# Atmega328.net
KiCad netlist of a schematic drawn in Altium Designer
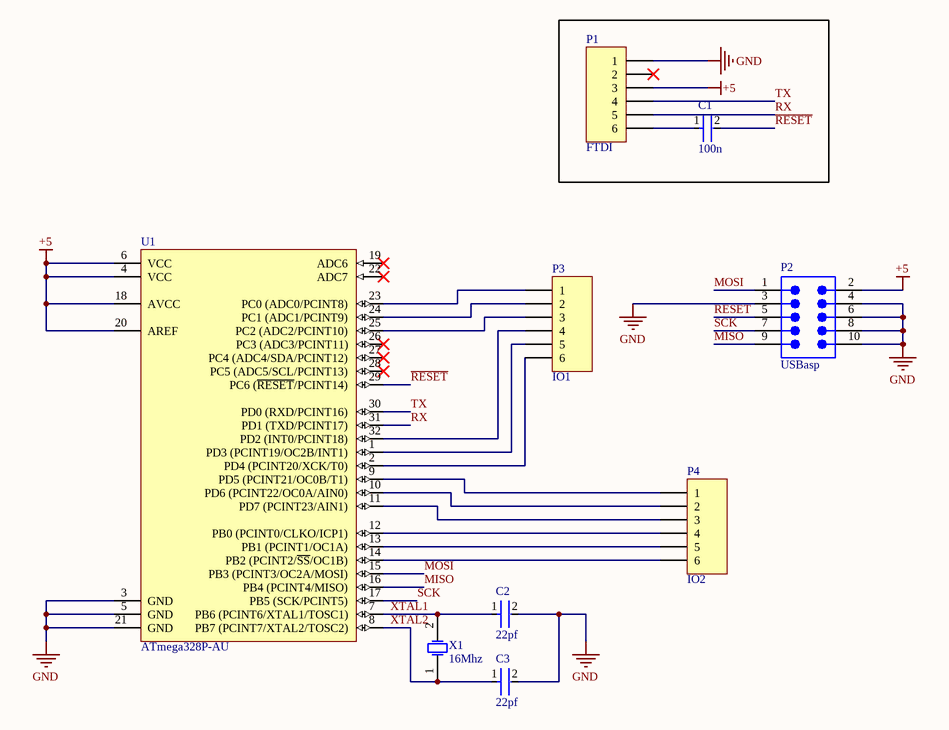
[diagram p0: Atmega328.SchDoc]

(export (version "E")
  (design (tool "Eeschema 10.0.6"))
  (components
    (comp (ref "C1")
      (value "100n")
      (footprint "FP-0805-L_2_01_0_2-W_1_25-IPC_B")
      (description "General Purpose Ceramic Capacitor, 0805, 100nF, 10%, X7R, 15%, 100V")
      (fields (field (name "VOLTAGE") "100V") (field (name "TOLERANCE") "10%"))
      (libsource (lib "Altium Content Vault") (part "b4654b650e69147ec39a6b967a45e02"))
    )
    (comp (ref "C2")
      (value "22pf")
      (footprint "FP-C0805C-DN-MFG")
      (description "Capacitor; Ceramic; Cap; 22.0pF; Tol 5%; SMT; Vol-Rtg 50V; C0G; Tape and Reel")
      (fields
        (field (name "OCTOPART") "https://octopart.com/c0805c220j5gactu-kemet-145470")
        (field (name "MANUFACTURER") "KEMET")
      )
      (libsource (lib "Altium Content Vault") (part "b4654b650e69147ec39a6b967a45e02"))
    )
    (comp (ref "C3")
      (value "22pf")
      (footprint "FP-C0805C-DN-MFG")
      (description "Capacitor; Ceramic; Cap; 22.0pF; Tol 5%; SMT; Vol-Rtg 50V; C0G; Tape and Reel")
      (fields
        (field (name "OCTOPART") "https://octopart.com/c0805c220j5gactu-kemet-145470")
        (field (name "MANUFACTURER") "KEMET")
      )
      (libsource (lib "Altium Content Vault") (part "b4654b650e69147ec39a6b967a45e02"))
    )
    (comp (ref "P1")
      (value "FTDI")
      (footprint "MHDR1X6")
      (description "Header, 6-Pin")
      (fields (field (name "PUBLISHER") "Altium Limited"))
      (libsource (lib "") (part "MHDR1X6_1"))
    )
    (comp (ref "P2")
      (value "USBasp")
      (footprint "61201021621")
      (libsource (lib "Altium Content Vault") (part "Header_Male_2R_10P"))
    )
    (comp (ref "P3")
      (value "IO1")
      (footprint "MHDR1X6")
      (description "Header, 6-Pin")
      (fields (field (name "PUBLISHER") "Altium Limited"))
      (libsource (lib "Miscellaneous Connectors") (part "MHDR1X6"))
    )
    (comp (ref "P4")
      (value "IO2")
      (footprint "MHDR1X6")
      (description "Header, 6-Pin")
      (fields (field (name "PUBLISHER") "Altium Limited"))
      (libsource (lib "Miscellaneous Connectors") (part "MHDR1X6"))
    )
    (comp (ref "U1")
      (value "ATmega328P-AU")
      (footprint "32A_M")
      (libsource (lib "Altium Content Vault") (part "MC-8B-ATM48-SQ32"))
    )
    (comp (ref "X1")
      (value "16Mhz")
      (footprint "FOX-FOXSDLF160-20_V")
      (libsource (lib "Altium Content Vault") (part "XTAL_1-2-2"))
    )
  )
  (nets
    (net (code "1") (name "+5") (class "Default")
      (node (ref "P1") (pin "3") (pinfunction "3_3") (pintype "passive"))
      (node (ref "P2") (pin "2") (pinfunction "2_2") (pintype "passive"))
      (node (ref "U1") (pin "18") (pinfunction "AVCC_18") (pintype "power_in"))
      (node (ref "U1") (pin "20") (pinfunction "AREF_20") (pintype "passive"))
      (node (ref "U1") (pin "4") (pinfunction "VCC_4") (pintype "power_in"))
      (node (ref "U1") (pin "6") (pinfunction "VCC_6") (pintype "power_in"))
    )
    (net (code "2") (name "/MISO") (class "Default")
      (node (ref "P2") (pin "9") (pinfunction "9_9") (pintype "passive"))
      (node (ref "U1") (pin "16") (pinfunction "PB4_(PCINT4/MISO)_16") (pintype "bidirectional"))
    )
    (net (code "3") (name "/MOSI") (class "Default")
      (node (ref "P2") (pin "1") (pinfunction "1_1") (pintype "passive"))
      (node (ref "U1") (pin "15") (pinfunction "PB3_(PCINT3/OC2A/MOSI)_15") (pintype "bidirectional"))
    )
    (net (code "4") (name "/RX") (class "Default")
      (node (ref "P1") (pin "5") (pinfunction "5_5") (pintype "passive"))
      (node (ref "U1") (pin "31") (pinfunction "PD1_(TXD/PCINT17)_31") (pintype "bidirectional"))
    )
    (net (code "5") (name "/SCK") (class "Default")
      (node (ref "P2") (pin "7") (pinfunction "7_7") (pintype "passive"))
      (node (ref "U1") (pin "17") (pinfunction "PB5_(SCK/PCINT5)_17") (pintype "bidirectional"))
    )
    (net (code "6") (name "/TX") (class "Default")
      (node (ref "P1") (pin "4") (pinfunction "4_4") (pintype "passive"))
      (node (ref "U1") (pin "30") (pinfunction "PD0_(RXD/PCINT16)_30") (pintype "bidirectional"))
    )
    (net (code "7") (name "/XTAL1") (class "Default")
      (node (ref "C2") (pin "1") (pinfunction "1_1") (pintype "passive"))
      (node (ref "U1") (pin "7") (pinfunction "PB6_(PCINT6/XTAL1/TOSC1)_7") (pintype "bidirectional"))
      (node (ref "X1") (pin "2") (pinfunction "X2_2") (pintype "passive"))
    )
    (net (code "8") (name "/XTAL2") (class "Default")
      (node (ref "C3") (pin "1") (pinfunction "1_1") (pintype "passive"))
      (node (ref "U1") (pin "8") (pinfunction "PB7_(PCINT7/XTAL2/TOSC2)_8") (pintype "bidirectional"))
      (node (ref "X1") (pin "1") (pinfunction "X1_1") (pintype "passive"))
    )
    (net (code "9") (name "/~{RESET}") (class "Default")
      (node (ref "C1") (pin "2") (pinfunction "2_2") (pintype "passive"))
      (node (ref "P2") (pin "5") (pinfunction "5_5") (pintype "passive"))
      (node (ref "U1") (pin "29") (pinfunction "PC6_(~{RESET}/PCINT14)_29") (pintype "bidirectional"))
    )
    (net (code "10") (name "GND") (class "Default")
      (node (ref "C2") (pin "2") (pinfunction "2_2") (pintype "passive"))
      (node (ref "C3") (pin "2") (pinfunction "2_2") (pintype "passive"))
      (node (ref "P1") (pin "1") (pinfunction "1_1") (pintype "passive"))
      (node (ref "P2") (pin "10") (pinfunction "10_10") (pintype "passive"))
      (node (ref "P2") (pin "3") (pinfunction "3_3") (pintype "passive"))
      (node (ref "P2") (pin "4") (pinfunction "4_4") (pintype "passive"))
      (node (ref "P2") (pin "6") (pinfunction "6_6") (pintype "passive"))
      (node (ref "P2") (pin "8") (pinfunction "8_8") (pintype "passive"))
      (node (ref "U1") (pin "21") (pinfunction "GND_21") (pintype "power_in"))
      (node (ref "U1") (pin "3") (pinfunction "GND_3") (pintype "power_in"))
      (node (ref "U1") (pin "5") (pinfunction "GND_5") (pintype "power_in"))
    )
    (net (code "11") (name "Net-(C1-Pad1)") (class "Default")
      (node (ref "C1") (pin "1") (pinfunction "1_1") (pintype "passive"))
      (node (ref "P1") (pin "6") (pinfunction "6_6") (pintype "passive"))
    )
    (net (code "12") (name "Net-(U1-PB0_(PCINT0{slash}CLKO{slash}ICP1))") (class "Default")
      (node (ref "P4") (pin "4") (pinfunction "4_4") (pintype "passive"))
      (node (ref "U1") (pin "12") (pinfunction "PB0_(PCINT0/CLKO/ICP1)_12") (pintype "bidirectional"))
    )
    (net (code "13") (name "Net-(U1-PB1_(PCINT1{slash}OC1A))") (class "Default")
      (node (ref "P4") (pin "5") (pinfunction "5_5") (pintype "passive"))
      (node (ref "U1") (pin "13") (pinfunction "PB1_(PCINT1/OC1A)_13") (pintype "bidirectional"))
    )
    (net (code "14") (name "Net-(U1-PB2_(PCINT2{slash}~{SS}{slash}OC1B))") (class "Default")
      (node (ref "P4") (pin "6") (pinfunction "6_6") (pintype "passive"))
      (node (ref "U1") (pin "14") (pinfunction "PB2_(PCINT2/~{SS}/OC1B)_14") (pintype "bidirectional"))
    )
    (net (code "15") (name "Net-(U1-PC0_(ADC0{slash}PCINT8))") (class "Default")
      (node (ref "P3") (pin "1") (pinfunction "1_1") (pintype "passive"))
      (node (ref "U1") (pin "23") (pinfunction "PC0_(ADC0/PCINT8)_23") (pintype "bidirectional"))
    )
    (net (code "16") (name "Net-(U1-PC1_(ADC1{slash}PCINT9))") (class "Default")
      (node (ref "P3") (pin "2") (pinfunction "2_2") (pintype "passive"))
      (node (ref "U1") (pin "24") (pinfunction "PC1_(ADC1/PCINT9)_24") (pintype "bidirectional"))
    )
    (net (code "17") (name "Net-(U1-PC2_(ADC2{slash}PCINT10))") (class "Default")
      (node (ref "P3") (pin "3") (pinfunction "3_3") (pintype "passive"))
      (node (ref "U1") (pin "25") (pinfunction "PC2_(ADC2/PCINT10)_25") (pintype "bidirectional"))
    )
    (net (code "18") (name "Net-(U1-PD2_(INT0{slash}PCINT18))") (class "Default")
      (node (ref "P3") (pin "4") (pinfunction "4_4") (pintype "passive"))
      (node (ref "U1") (pin "32") (pinfunction "PD2_(INT0/PCINT18)_32") (pintype "bidirectional"))
    )
    (net (code "19") (name "Net-(U1-PD3_(PCINT19{slash}OC2B{slash}INT1))") (class "Default")
      (node (ref "P3") (pin "5") (pinfunction "5_5") (pintype "passive"))
      (node (ref "U1") (pin "1") (pinfunction "PD3_(PCINT19/OC2B/INT1)_1") (pintype "bidirectional"))
    )
    (net (code "20") (name "Net-(U1-PD4_(PCINT20{slash}XCK{slash}T0))") (class "Default")
      (node (ref "P3") (pin "6") (pinfunction "6_6") (pintype "passive"))
      (node (ref "U1") (pin "2") (pinfunction "PD4_(PCINT20/XCK/T0)_2") (pintype "bidirectional"))
    )
    (net (code "21") (name "Net-(U1-PD5_(PCINT21{slash}OC0B{slash}T1))") (class "Default")
      (node (ref "P4") (pin "1") (pinfunction "1_1") (pintype "passive"))
      (node (ref "U1") (pin "9") (pinfunction "PD5_(PCINT21/OC0B/T1)_9") (pintype "bidirectional"))
    )
    (net (code "22") (name "Net-(U1-PD6_(PCINT22{slash}OC0A{slash}AIN0))") (class "Default")
      (node (ref "P4") (pin "2") (pinfunction "2_2") (pintype "passive"))
      (node (ref "U1") (pin "10") (pinfunction "PD6_(PCINT22/OC0A/AIN0)_10") (pintype "bidirectional"))
    )
    (net (code "23") (name "Net-(U1-PD7_(PCINT23{slash}AIN1))") (class "Default")
      (node (ref "P4") (pin "3") (pinfunction "3_3") (pintype "passive"))
      (node (ref "U1") (pin "11") (pinfunction "PD7_(PCINT23/AIN1)_11") (pintype "bidirectional"))
    )
    (net (code "24") (name "unconnected-(P1-Pad2)") (class "Default")
      (node (ref "P1") (pin "2") (pinfunction "2_2") (pintype "passive+no_connect"))
    )
    (net (code "25") (name "unconnected-(U1-ADC6-Pad19)") (class "Default")
      (node (ref "U1") (pin "19") (pinfunction "ADC6_19") (pintype "input+no_connect"))
    )
    (net (code "26") (name "unconnected-(U1-ADC7-Pad22)") (class "Default")
      (node (ref "U1") (pin "22") (pinfunction "ADC7_22") (pintype "input+no_connect"))
    )
    (net (code "27") (name "unconnected-(U1-PC3_(ADC3{slash}PCINT11)-Pad26)") (class "Default")
      (node (ref "U1") (pin "26") (pinfunction "PC3_(ADC3/PCINT11)_26") (pintype "bidirectional+no_connect"))
    )
    (net (code "28") (name "unconnected-(U1-PC4_(ADC4{slash}SDA{slash}PCINT12)-Pad27)") (class "Default")
      (node (ref "U1") (pin "27") (pinfunction "PC4_(ADC4/SDA/PCINT12)_27") (pintype "bidirectional+no_connect"))
    )
    (net (code "29") (name "unconnected-(U1-PC5_(ADC5{slash}SCL{slash}PCINT13)-Pad28)") (class "Default")
      (node (ref "U1") (pin "28") (pinfunction "PC5_(ADC5/SCL/PCINT13)_28") (pintype "bidirectional+no_connect"))
    )
  )
)
